# Sheet2.net
KiCad netlist of a schematic drawn in Altium Designer
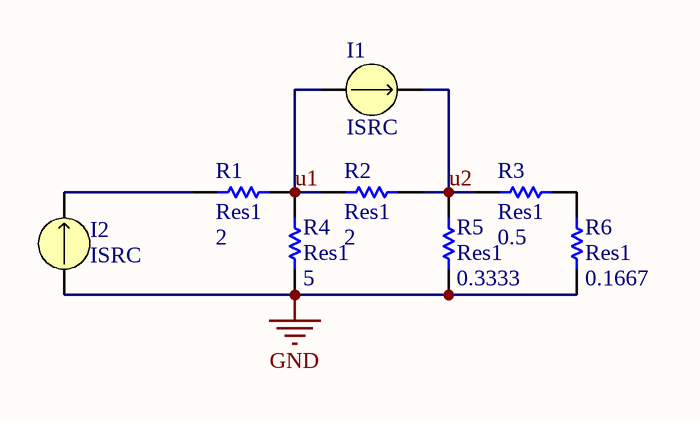
[diagram p0: Sheet2.SchDoc]

(export (version "E")
  (design (tool "Eeschema 10.0.6"))
  (components
    (comp (ref "I1")
      (value "ISRC")
      (description "Current Source")
      (fields (field (name "PUBLISHER") "Altium Limited"))
      (libsource (lib "Simulation Sources") (part "ISRC"))
    )
    (comp (ref "I2")
      (value "ISRC")
      (description "Current Source")
      (fields (field (name "PUBLISHER") "Altium Limited"))
      (libsource (lib "Simulation Sources") (part "ISRC"))
    )
    (comp (ref "R1")
      (value "Res1")
      (footprint "AXIAL-0.3")
      (description "Resistor")
      (fields (field (name "ALTIUM_VALUE") "2") (field (name "PUBLISHER") "Altium Limited"))
      (libsource (lib "Miscellaneous Devices") (part "Res1"))
    )
    (comp (ref "R2")
      (value "Res1")
      (footprint "AXIAL-0.3")
      (description "Resistor")
      (fields (field (name "ALTIUM_VALUE") "2") (field (name "PUBLISHER") "Altium Limited"))
      (libsource (lib "Miscellaneous Devices") (part "Res1"))
    )
    (comp (ref "R3")
      (value "Res1")
      (footprint "AXIAL-0.3")
      (description "Resistor")
      (fields (field (name "ALTIUM_VALUE") "0.5") (field (name "PUBLISHER") "Altium Limited"))
      (libsource (lib "Miscellaneous Devices") (part "Res1"))
    )
    (comp (ref "R4")
      (value "Res1")
      (footprint "AXIAL-0.3")
      (description "Resistor")
      (fields (field (name "ALTIUM_VALUE") "5") (field (name "PUBLISHER") "Altium Limited"))
      (libsource (lib "Miscellaneous Devices") (part "Res1"))
    )
    (comp (ref "R5")
      (value "Res1")
      (footprint "AXIAL-0.3")
      (description "Resistor")
      (fields (field (name "ALTIUM_VALUE") "0.3333") (field (name "PUBLISHER") "Altium Limited"))
      (libsource (lib "Miscellaneous Devices") (part "Res1"))
    )
    (comp (ref "R6")
      (value "Res1")
      (footprint "AXIAL-0.3")
      (description "Resistor")
      (fields (field (name "ALTIUM_VALUE") "0.1667") (field (name "PUBLISHER") "Altium Limited"))
      (libsource (lib "Miscellaneous Devices") (part "Res1"))
    )
  )
  (nets
    (net (code "1") (name "/u1") (class "Default")
      (node (ref "I1") (pin "1") (pinfunction "1_1") (pintype "passive"))
      (node (ref "R1") (pin "2") (pinfunction "2_2") (pintype "passive"))
      (node (ref "R2") (pin "1") (pinfunction "1_1") (pintype "passive"))
      (node (ref "R4") (pin "2") (pinfunction "2_2") (pintype "passive"))
    )
    (net (code "2") (name "/u2") (class "Default")
      (node (ref "I1") (pin "2") (pinfunction "2_2") (pintype "passive"))
      (node (ref "R2") (pin "2") (pinfunction "2_2") (pintype "passive"))
      (node (ref "R3") (pin "1") (pinfunction "1_1") (pintype "passive"))
      (node (ref "R5") (pin "2") (pinfunction "2_2") (pintype "passive"))
    )
    (net (code "3") (name "GND") (class "Default")
      (node (ref "I2") (pin "1") (pinfunction "1_1") (pintype "passive"))
      (node (ref "R4") (pin "1") (pinfunction "1_1") (pintype "passive"))
      (node (ref "R5") (pin "1") (pinfunction "1_1") (pintype "passive"))
      (node (ref "R6") (pin "1") (pinfunction "1_1") (pintype "passive"))
    )
    (net (code "4") (name "Net-(I2-Pad2)") (class "Default")
      (node (ref "I2") (pin "2") (pinfunction "2_2") (pintype "passive"))
      (node (ref "R1") (pin "1") (pinfunction "1_1") (pintype "passive"))
    )
    (net (code "5") (name "Net-(R3-Pad2)") (class "Default")
      (node (ref "R3") (pin "2") (pinfunction "2_2") (pintype "passive"))
      (node (ref "R6") (pin "2") (pinfunction "2_2") (pintype "passive"))
    )
  )
)
